# TTLclock.net
KiCad netlist of a schematic drawn in Altium Designer
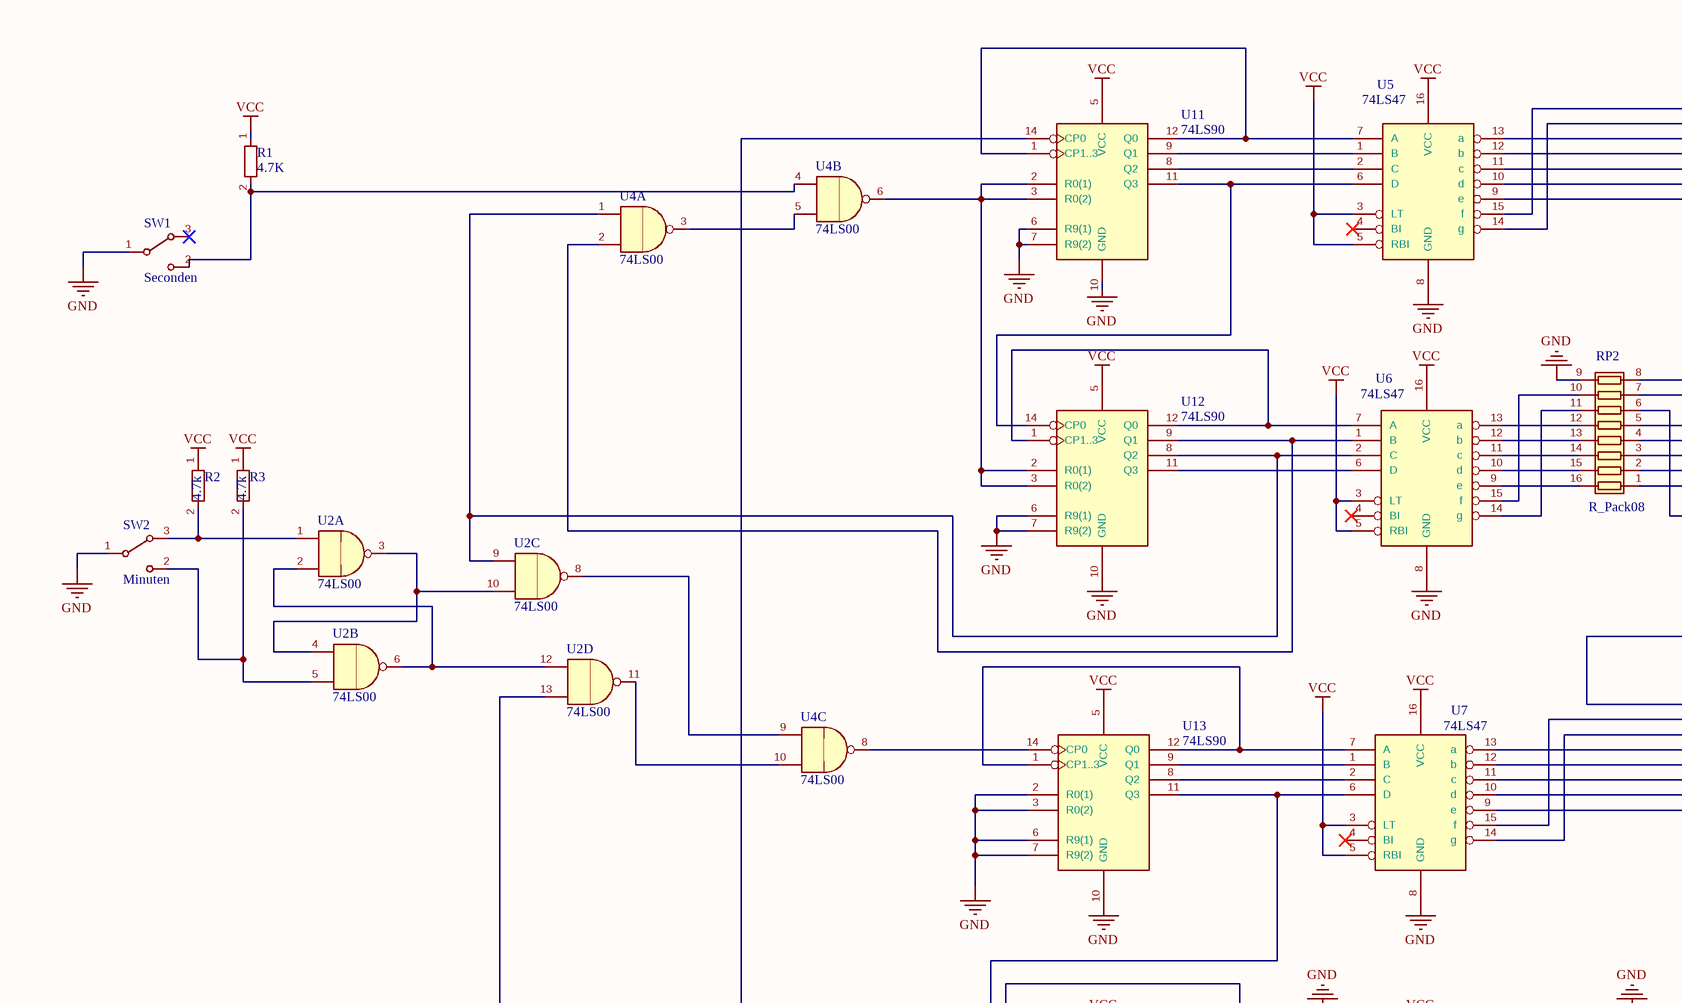
[diagram p0: TTLclock.SchDoc, top left]
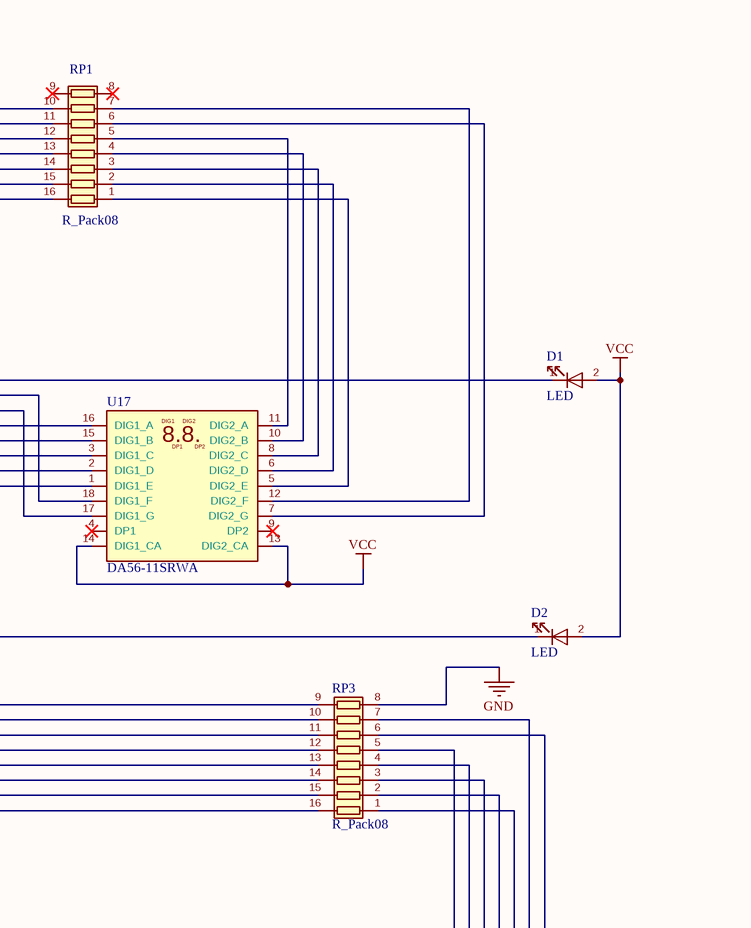
[diagram p1: TTLclock.SchDoc, top right]
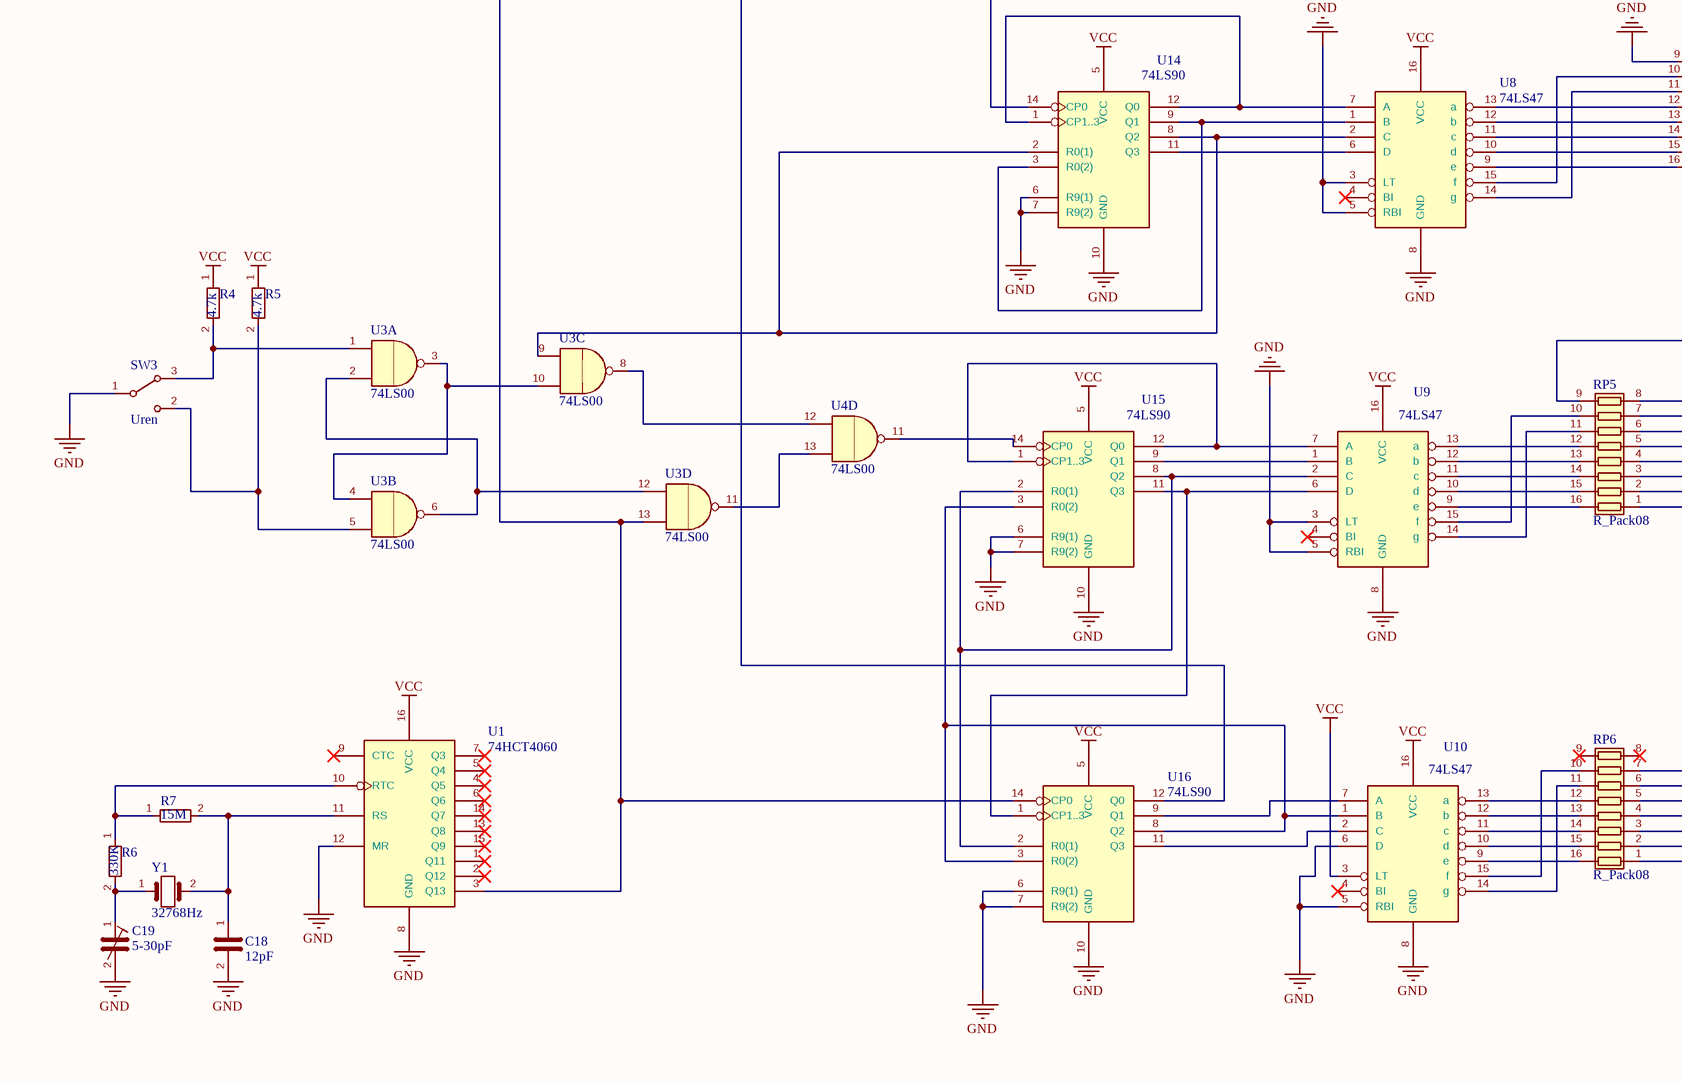
[diagram p2: TTLclock.SchDoc, bottom left]
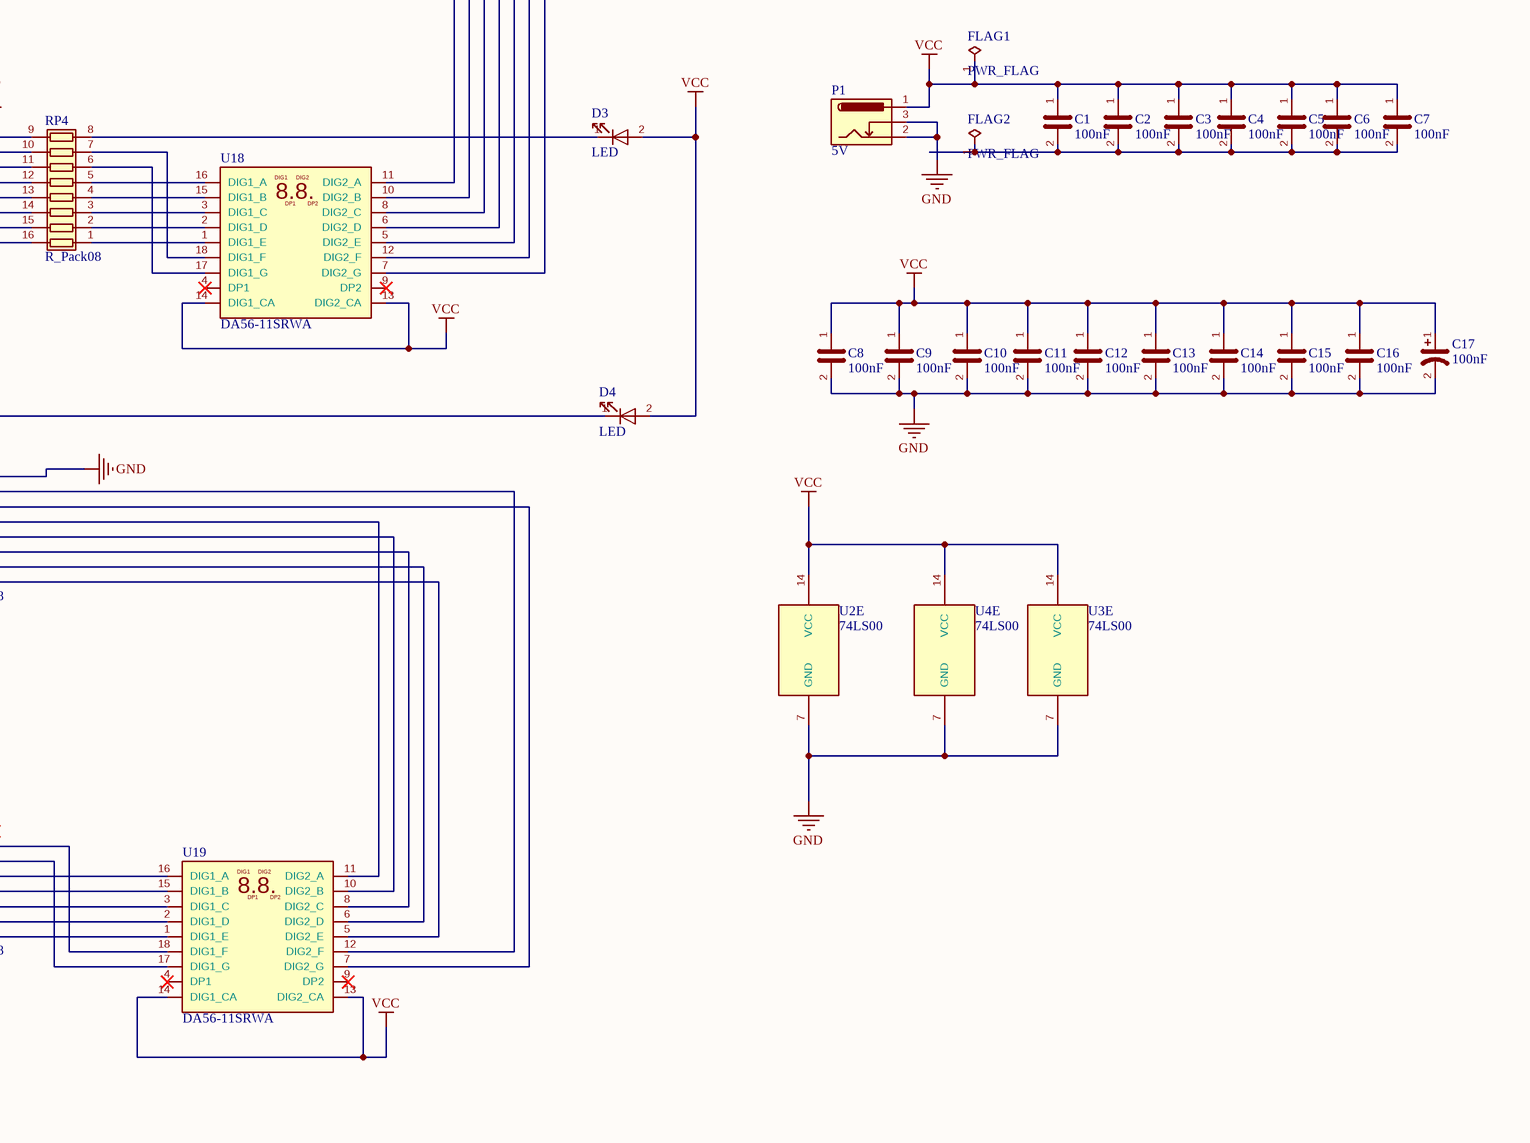
[diagram p3: TTLclock.SchDoc, bottom right]

(export (version "E")
  (design (tool "Eeschema 10.0.6"))
  (components
    (comp (ref "C1")
      (value "100nF")
      (footprint "CAPPA1420W55L380D260")
      (libsource (lib "ttl_clock") (part "C"))
    )
    (comp (ref "C2")
      (value "100nF")
      (footprint "CAPPA1420W55L380D260")
      (libsource (lib "ttl_clock") (part "C"))
    )
    (comp (ref "C3")
      (value "100nF")
      (footprint "CAPPA1420W55L380D260")
      (libsource (lib "ttl_clock") (part "C"))
    )
    (comp (ref "C4")
      (value "100nF")
      (footprint "CAPPA1420W55L380D260")
      (libsource (lib "ttl_clock") (part "C"))
    )
    (comp (ref "C5")
      (value "100nF")
      (footprint "CAPPA1420W55L380D260")
      (libsource (lib "ttl_clock") (part "C"))
    )
    (comp (ref "C6")
      (value "100nF")
      (footprint "CAPPA1420W55L380D260")
      (libsource (lib "ttl_clock") (part "C"))
    )
    (comp (ref "C7")
      (value "100nF")
      (footprint "CAPPA1420W55L380D260")
      (libsource (lib "ttl_clock") (part "C"))
    )
    (comp (ref "C8")
      (value "100nF")
      (footprint "CAPPA1420W55L380D260")
      (libsource (lib "ttl_clock") (part "C"))
    )
    (comp (ref "C9")
      (value "100nF")
      (footprint "CAPPA1420W55L380D260")
      (libsource (lib "ttl_clock") (part "C"))
    )
    (comp (ref "C10")
      (value "100nF")
      (footprint "CAPPA1420W55L380D260")
      (libsource (lib "ttl_clock") (part "C"))
    )
    (comp (ref "C11")
      (value "100nF")
      (footprint "CAPPA1420W55L380D260")
      (libsource (lib "ttl_clock") (part "C"))
    )
    (comp (ref "C12")
      (value "100nF")
      (footprint "CAPPA1420W55L380D260")
      (libsource (lib "ttl_clock") (part "C"))
    )
    (comp (ref "C13")
      (value "100nF")
      (footprint "CAPPA1420W55L380D260")
      (libsource (lib "ttl_clock") (part "C"))
    )
    (comp (ref "C14")
      (value "100nF")
      (footprint "CAPPA1420W55L380D260")
      (libsource (lib "ttl_clock") (part "C"))
    )
    (comp (ref "C15")
      (value "100nF")
      (footprint "CAPPA1420W55L380D260")
      (libsource (lib "ttl_clock") (part "C"))
    )
    (comp (ref "C16")
      (value "100nF")
      (footprint "CAPPA1420W55L380D260")
      (libsource (lib "ttl_clock") (part "C"))
    )
    (comp (ref "C17")
      (value "100nF")
      (footprint "CAPPRD250W52D630H1250")
      (libsource (lib "ttl_clock") (part "CP1"))
    )
    (comp (ref "C18") (value "12pF") (footprint "FG28") (libsource (lib "ttl_clock") (part "C")))
    (comp (ref "C19") (value "5-30pF") (footprint "JZ300") (libsource (lib "ttl_clock") (part "CTRIM")))
    (comp (ref "D1")
      (value "LED")
      (footprint "LED_SSL-LX4673GD-LA20")
      (libsource (lib "ttl_clock") (part "LED"))
    )
    (comp (ref "D2")
      (value "LED")
      (footprint "LED_SSL-LX4673GD-LA20")
      (libsource (lib "ttl_clock") (part "LED"))
    )
    (comp (ref "D3")
      (value "LED")
      (footprint "LED_SSL-LX4673GD-LA20")
      (libsource (lib "ttl_clock") (part "LED"))
    )
    (comp (ref "D4")
      (value "LED")
      (footprint "LED_SSL-LX4673GD-LA20")
      (libsource (lib "ttl_clock") (part "LED"))
    )
    (comp (ref "FLAG1") (value "PWR_FLAG") (libsource (lib "ttl_clock") (part "PWR_FLAG")))
    (comp (ref "FLAG2") (value "PWR_FLAG") (libsource (lib "ttl_clock") (part "PWR_FLAG")))
    (comp (ref "P1")
      (value "5V")
      (footprint "KLDX0202A")
      (libsource (lib "ttl_clock") (part "Barrel_Jack_Switch"))
    )
    (comp (ref "R1")
      (value "4.7K")
      (footprint "RESAD2870W80L1190D420")
      (libsource (lib "ttl_clock") (part "R"))
    )
    (comp (ref "R2")
      (value "4.7k")
      (footprint "RESAD2870W80L1190D420")
      (libsource (lib "ttl_clock") (part "R"))
    )
    (comp (ref "R3")
      (value "4.7k")
      (footprint "RESAD2870W80L1190D420")
      (libsource (lib "ttl_clock") (part "R"))
    )
    (comp (ref "R4")
      (value "4.7k")
      (footprint "RESAD2870W80L1190D420")
      (libsource (lib "ttl_clock") (part "R"))
    )
    (comp (ref "R5")
      (value "4.7k")
      (footprint "RESAD2870W80L1190D420")
      (libsource (lib "ttl_clock") (part "R"))
    )
    (comp (ref "R6")
      (value "330K")
      (footprint "RESAD2870W80L1190D420")
      (libsource (lib "ttl_clock") (part "R"))
    )
    (comp (ref "R7") (value "15M") (footprint "RESAD2870W80L1190D420") (libsource (lib "") (part "R_1")))
    (comp (ref "RP1")
      (value "R_Pack08")
      (footprint "DIP787W49P254L2197H469Q16N")
      (libsource (lib "ttl_clock") (part "R_Pack08"))
    )
    (comp (ref "RP2")
      (value "R_Pack08")
      (footprint "DIP787W49P254L2197H469Q16N")
      (libsource (lib "ttl_clock") (part "R_Pack08"))
    )
    (comp (ref "RP3")
      (value "R_Pack08")
      (footprint "DIP787W49P254L2197H469Q16N")
      (libsource (lib "ttl_clock") (part "R_Pack08"))
    )
    (comp (ref "RP4")
      (value "R_Pack08")
      (footprint "DIP787W49P254L2197H469Q16N")
      (libsource (lib "ttl_clock") (part "R_Pack08"))
    )
    (comp (ref "RP5")
      (value "R_Pack08")
      (footprint "DIP787W49P254L2197H469Q16N")
      (libsource (lib "ttl_clock") (part "R_Pack08"))
    )
    (comp (ref "RP6")
      (value "R_Pack08")
      (footprint "DIP787W49P254L2197H469Q16N")
      (libsource (lib "ttl_clock") (part "R_Pack08"))
    )
    (comp (ref "SW1")
      (value "Seconden")
      (footprint "SS0750301F040P1A")
      (libsource (lib "ttl_clock") (part "SW_SPDT_Omron"))
    )
    (comp (ref "SW2")
      (value "Minuten")
      (footprint "SS0750301F040P1A")
      (libsource (lib "ttl_clock") (part "SW_SPDT_Omron"))
    )
    (comp (ref "SW3")
      (value "Uren")
      (footprint "SS0750301F040P1A")
      (libsource (lib "ttl_clock") (part "SW_SPDT_Omron"))
    )
    (comp (ref "U1")
      (value "74HCT4060")
      (footprint "DIP794W53P254L1930H508Q16N")
      (libsource (lib "ttl_clock") (part "74HCT4060"))
    )
    (comp (ref "U2")
      (value "74LS00")
      (footprint "DIP794W53P254L1930H508Q14N")
      (libsource (lib "ttl_clock") (part "74LS00"))
    )
    (comp (ref "U3")
      (value "74LS00")
      (footprint "DIP794W53P254L1930H508Q14N")
      (libsource (lib "ttl_clock") (part "74LS00"))
    )
    (comp (ref "U4")
      (value "74LS00")
      (footprint "DIP794W53P254L1930H508Q14N")
      (libsource (lib "ttl_clock") (part "74LS00"))
    )
    (comp (ref "U5")
      (value "74LS47")
      (footprint "DIP794W53P254L1930H508Q16N")
      (libsource (lib "ttl_clock") (part "74LS47"))
    )
    (comp (ref "U6")
      (value "74LS47")
      (footprint "DIP794W53P254L1930H508Q16N")
      (libsource (lib "ttl_clock") (part "74LS47"))
    )
    (comp (ref "U7")
      (value "74LS47")
      (footprint "DIP794W53P254L1930H508Q16N")
      (libsource (lib "ttl_clock") (part "74LS47"))
    )
    (comp (ref "U8")
      (value "74LS47")
      (footprint "DIP794W53P254L1930H508Q16N")
      (libsource (lib "ttl_clock") (part "74LS47"))
    )
    (comp (ref "U9")
      (value "74LS47")
      (footprint "DIP794W53P254L1930H508Q16N")
      (libsource (lib "ttl_clock") (part "74LS47"))
    )
    (comp (ref "U10")
      (value "74LS47")
      (footprint "DIP794W53P254L1930H508Q16N")
      (libsource (lib "ttl_clock") (part "74LS47"))
    )
    (comp (ref "U11")
      (value "74LS90")
      (footprint "DIP794W53P254L1930H508Q14N")
      (libsource (lib "ttl_clock") (part "74LS90"))
    )
    (comp (ref "U12")
      (value "74LS90")
      (footprint "DIP794W53P254L1930H508Q14N")
      (libsource (lib "ttl_clock") (part "74LS90"))
    )
    (comp (ref "U13")
      (value "74LS90")
      (footprint "DIP794W53P254L1930H508Q14N")
      (libsource (lib "ttl_clock") (part "74LS90"))
    )
    (comp (ref "U14")
      (value "74LS90")
      (footprint "DIP794W53P254L1930H508Q14N")
      (libsource (lib "ttl_clock") (part "74LS90"))
    )
    (comp (ref "U15")
      (value "74LS90")
      (footprint "DIP794W53P254L1930H508Q14N")
      (libsource (lib "ttl_clock") (part "74LS90"))
    )
    (comp (ref "U16")
      (value "74LS90")
      (footprint "DIP794W53P254L1930H508Q14N")
      (libsource (lib "ttl_clock") (part "74LS90"))
    )
    (comp (ref "U17")
      (value "DA56-11SRWA")
      (footprint "DIPS1524W50P254L2500H825Q18N")
      (libsource (lib "ttl_clock") (part "DA56-11SRWA"))
    )
    (comp (ref "U18")
      (value "DA56-11SRWA")
      (footprint "DIPS1524W50P254L2500H825Q18N")
      (libsource (lib "ttl_clock") (part "DA56-11SRWA"))
    )
    (comp (ref "U19")
      (value "DA56-11SRWA")
      (footprint "DIPS1524W50P254L2500H825Q18N")
      (libsource (lib "ttl_clock") (part "DA56-11SRWA"))
    )
    (comp (ref "Y1")
      (value "32768Hz")
      (footprint "XTAL_AB26T-32.768KHZ")
      (libsource (lib "ttl_clock") (part "Crystal"))
    )
  )
  (nets
    (net (code "1") (name "GND") (class "Default")
      (node (ref "C10") (pin "2") (pinfunction "2_2") (pintype "passive"))
      (node (ref "C11") (pin "2") (pinfunction "2_2") (pintype "passive"))
      (node (ref "C12") (pin "2") (pinfunction "2_2") (pintype "passive"))
      (node (ref "C13") (pin "2") (pinfunction "2_2") (pintype "passive"))
      (node (ref "C14") (pin "2") (pinfunction "2_2") (pintype "passive"))
      (node (ref "C15") (pin "2") (pinfunction "2_2") (pintype "passive"))
      (node (ref "C16") (pin "2") (pinfunction "2_2") (pintype "passive"))
      (node (ref "C17") (pin "2") (pinfunction "2_2") (pintype "passive"))
      (node (ref "C18") (pin "2") (pinfunction "2_2") (pintype "passive"))
      (node (ref "C19") (pin "2") (pinfunction "2_2") (pintype "passive"))
      (node (ref "C8") (pin "2") (pinfunction "2_2") (pintype "passive"))
      (node (ref "C9") (pin "2") (pinfunction "2_2") (pintype "passive"))
      (node (ref "P1") (pin "2") (pinfunction "2_2") (pintype "passive"))
      (node (ref "P1") (pin "3") (pinfunction "3_3") (pintype "passive"))
      (node (ref "RP2") (pin "9") (pinfunction "R8.2_9") (pintype "passive"))
      (node (ref "RP3") (pin "8") (pinfunction "R8.1_8") (pintype "passive"))
      (node (ref "RP4") (pin "9") (pinfunction "R8.2_9") (pintype "passive"))
      (node (ref "RP5") (pin "8") (pinfunction "R8.1_8") (pintype "passive"))
      (node (ref "SW1") (pin "1") (pinfunction "B_1") (pintype "passive"))
      (node (ref "SW2") (pin "1") (pinfunction "B_1") (pintype "passive"))
      (node (ref "SW3") (pin "1") (pinfunction "B_1") (pintype "passive"))
      (node (ref "U1") (pin "12") (pinfunction "MR_12") (pintype "passive"))
      (node (ref "U1") (pin "8") (pinfunction "GND_8") (pintype "passive"))
      (node (ref "U10") (pin "5") (pinfunction "RBI_5") (pintype "passive"))
      (node (ref "U10") (pin "6") (pinfunction "D_6") (pintype "passive"))
      (node (ref "U10") (pin "8") (pinfunction "GND_8") (pintype "passive"))
      (node (ref "U11") (pin "10") (pinfunction "GND_10") (pintype "passive"))
      (node (ref "U11") (pin "6") (pinfunction "R9(1)_6") (pintype "passive"))
      (node (ref "U11") (pin "7") (pinfunction "R9(2)_7") (pintype "passive"))
      (node (ref "U12") (pin "10") (pinfunction "GND_10") (pintype "passive"))
      (node (ref "U12") (pin "6") (pinfunction "R9(1)_6") (pintype "passive"))
      (node (ref "U12") (pin "7") (pinfunction "R9(2)_7") (pintype "passive"))
      (node (ref "U13") (pin "10") (pinfunction "GND_10") (pintype "passive"))
      (node (ref "U13") (pin "2") (pinfunction "R0(1)_2") (pintype "passive"))
      (node (ref "U13") (pin "3") (pinfunction "R0(2)_3") (pintype "passive"))
      (node (ref "U13") (pin "6") (pinfunction "R9(1)_6") (pintype "passive"))
      (node (ref "U13") (pin "7") (pinfunction "R9(2)_7") (pintype "passive"))
      (node (ref "U14") (pin "10") (pinfunction "GND_10") (pintype "passive"))
      (node (ref "U14") (pin "6") (pinfunction "R9(1)_6") (pintype "passive"))
      (node (ref "U14") (pin "7") (pinfunction "R9(2)_7") (pintype "passive"))
      (node (ref "U15") (pin "10") (pinfunction "GND_10") (pintype "passive"))
      (node (ref "U15") (pin "6") (pinfunction "R9(1)_6") (pintype "passive"))
      (node (ref "U15") (pin "7") (pinfunction "R9(2)_7") (pintype "passive"))
      (node (ref "U16") (pin "10") (pinfunction "GND_10") (pintype "passive"))
      (node (ref "U16") (pin "6") (pinfunction "R9(1)_6") (pintype "passive"))
      (node (ref "U16") (pin "7") (pinfunction "R9(2)_7") (pintype "passive"))
      (node (ref "U2") (pin "7") (pinfunction "GND_7") (pintype "passive"))
      (node (ref "U3") (pin "7") (pinfunction "GND_7") (pintype "passive"))
      (node (ref "U4") (pin "7") (pinfunction "GND_7") (pintype "passive"))
      (node (ref "U5") (pin "8") (pinfunction "GND_8") (pintype "passive"))
      (node (ref "U6") (pin "8") (pinfunction "GND_8") (pintype "passive"))
      (node (ref "U7") (pin "8") (pinfunction "GND_8") (pintype "passive"))
      (node (ref "U8") (pin "3") (pinfunction "LT_3") (pintype "passive"))
      (node (ref "U8") (pin "5") (pinfunction "RBI_5") (pintype "passive"))
      (node (ref "U8") (pin "8") (pinfunction "GND_8") (pintype "passive"))
      (node (ref "U9") (pin "3") (pinfunction "LT_3") (pintype "passive"))
      (node (ref "U9") (pin "5") (pinfunction "RBI_5") (pintype "passive"))
      (node (ref "U9") (pin "8") (pinfunction "GND_8") (pintype "passive"))
    )
    (net (code "2") (name "Net-(C19-Pad1)") (class "Default")
      (node (ref "C19") (pin "1") (pinfunction "1_1") (pintype "passive"))
      (node (ref "R6") (pin "2") (pinfunction "2_2") (pintype "passive"))
      (node (ref "Y1") (pin "1") (pinfunction "1_1") (pintype "passive"))
    )
    (net (code "3") (name "Net-(D1-K)") (class "Default")
      (node (ref "D1") (pin "1") (pinfunction "K_1") (pintype "passive"))
      (node (ref "RP2") (pin "8") (pinfunction "R8.1_8") (pintype "passive"))
    )
    (net (code "4") (name "Net-(D2-K)") (class "Default")
      (node (ref "D2") (pin "1") (pinfunction "K_1") (pintype "passive"))
      (node (ref "RP3") (pin "9") (pinfunction "R8.2_9") (pintype "passive"))
    )
    (net (code "5") (name "Net-(D3-K)") (class "Default")
      (node (ref "D3") (pin "1") (pinfunction "K_1") (pintype "passive"))
      (node (ref "RP4") (pin "8") (pinfunction "R8.1_8") (pintype "passive"))
    )
    (net (code "6") (name "Net-(D4-K)") (class "Default")
      (node (ref "D4") (pin "1") (pinfunction "K_1") (pintype "passive"))
      (node (ref "RP5") (pin "9") (pinfunction "R8.2_9") (pintype "passive"))
    )
    (net (code "7") (name "Net-(FLAG2-pwr)") (class "Default")
      (node (ref "C1") (pin "2") (pinfunction "2_2") (pintype "passive"))
      (node (ref "C2") (pin "2") (pinfunction "2_2") (pintype "passive"))
      (node (ref "C3") (pin "2") (pinfunction "2_2") (pintype "passive"))
      (node (ref "C4") (pin "2") (pinfunction "2_2") (pintype "passive"))
      (node (ref "C5") (pin "2") (pinfunction "2_2") (pintype "passive"))
      (node (ref "C6") (pin "2") (pinfunction "2_2") (pintype "passive"))
      (node (ref "C7") (pin "2") (pinfunction "2_2") (pintype "passive"))
      (node (ref "FLAG2") (pin "1") (pinfunction "pwr_1") (pintype "passive"))
    )
    (net (code "8") (name "Net-(RP1-R1.1)") (class "Default")
      (node (ref "RP1") (pin "1") (pinfunction "R1.1_1") (pintype "passive"))
      (node (ref "U17") (pin "5") (pinfunction "DIG2_E_5") (pintype "passive"))
    )
    (net (code "9") (name "Net-(RP1-R1.2)") (class "Default")
      (node (ref "RP1") (pin "16") (pinfunction "R1.2_16") (pintype "passive"))
      (node (ref "U5") (pin "9") (pinfunction "e_9") (pintype "passive"))
    )
    (net (code "10") (name "Net-(RP1-R2.1)") (class "Default")
      (node (ref "RP1") (pin "2") (pinfunction "R2.1_2") (pintype "passive"))
      (node (ref "U17") (pin "6") (pinfunction "DIG2_D_6") (pintype "passive"))
    )
    (net (code "11") (name "Net-(RP1-R2.2)") (class "Default")
      (node (ref "RP1") (pin "15") (pinfunction "R2.2_15") (pintype "passive"))
      (node (ref "U5") (pin "10") (pinfunction "d_10") (pintype "passive"))
    )
    (net (code "12") (name "Net-(RP1-R3.1)") (class "Default")
      (node (ref "RP1") (pin "3") (pinfunction "R3.1_3") (pintype "passive"))
      (node (ref "U17") (pin "8") (pinfunction "DIG2_C_8") (pintype "passive"))
    )
    (net (code "13") (name "Net-(RP1-R3.2)") (class "Default")
      (node (ref "RP1") (pin "14") (pinfunction "R3.2_14") (pintype "passive"))
      (node (ref "U5") (pin "11") (pinfunction "c_11") (pintype "passive"))
    )
    (net (code "14") (name "Net-(RP1-R4.1)") (class "Default")
      (node (ref "RP1") (pin "4") (pinfunction "R4.1_4") (pintype "passive"))
      (node (ref "U17") (pin "10") (pinfunction "DIG2_B_10") (pintype "passive"))
    )
    (net (code "15") (name "Net-(RP1-R4.2)") (class "Default")
      (node (ref "RP1") (pin "13") (pinfunction "R4.2_13") (pintype "passive"))
      (node (ref "U5") (pin "12") (pinfunction "b_12") (pintype "passive"))
    )
    (net (code "16") (name "Net-(RP1-R5.1)") (class "Default")
      (node (ref "RP1") (pin "5") (pinfunction "R5.1_5") (pintype "passive"))
      (node (ref "U17") (pin "11") (pinfunction "DIG2_A_11") (pintype "passive"))
    )
    (net (code "17") (name "Net-(RP1-R5.2)") (class "Default")
      (node (ref "RP1") (pin "12") (pinfunction "R5.2_12") (pintype "passive"))
      (node (ref "U5") (pin "13") (pinfunction "a_13") (pintype "passive"))
    )
    (net (code "18") (name "Net-(RP1-R6.1)") (class "Default")
      (node (ref "RP1") (pin "6") (pinfunction "R6.1_6") (pintype "passive"))
      (node (ref "U17") (pin "7") (pinfunction "DIG2_G_7") (pintype "passive"))
    )
    (net (code "19") (name "Net-(RP1-R6.2)") (class "Default")
      (node (ref "RP1") (pin "11") (pinfunction "R6.2_11") (pintype "passive"))
      (node (ref "U5") (pin "14") (pinfunction "g_14") (pintype "passive"))
    )
    (net (code "20") (name "Net-(RP1-R7.1)") (class "Default")
      (node (ref "RP1") (pin "7") (pinfunction "R7.1_7") (pintype "passive"))
      (node (ref "U17") (pin "12") (pinfunction "DIG2_F_12") (pintype "passive"))
    )
    (net (code "21") (name "Net-(RP1-R7.2)") (class "Default")
      (node (ref "RP1") (pin "10") (pinfunction "R7.2_10") (pintype "passive"))
      (node (ref "U5") (pin "15") (pinfunction "f_15") (pintype "passive"))
    )
    (net (code "22") (name "Net-(RP2-R1.1)") (class "Default")
      (node (ref "RP2") (pin "1") (pinfunction "R1.1_1") (pintype "passive"))
      (node (ref "U17") (pin "1") (pinfunction "DIG1_E_1") (pintype "passive"))
    )
    (net (code "23") (name "Net-(RP2-R1.2)") (class "Default")
      (node (ref "RP2") (pin "16") (pinfunction "R1.2_16") (pintype "passive"))
      (node (ref "U6") (pin "9") (pinfunction "e_9") (pintype "passive"))
    )
    (net (code "24") (name "Net-(RP2-R2.1)") (class "Default")
      (node (ref "RP2") (pin "2") (pinfunction "R2.1_2") (pintype "passive"))
      (node (ref "U17") (pin "2") (pinfunction "DIG1_D_2") (pintype "passive"))
    )
    (net (code "25") (name "Net-(RP2-R2.2)") (class "Default")
      (node (ref "RP2") (pin "15") (pinfunction "R2.2_15") (pintype "passive"))
      (node (ref "U6") (pin "10") (pinfunction "d_10") (pintype "passive"))
    )
    (net (code "26") (name "Net-(RP2-R3.1)") (class "Default")
      (node (ref "RP2") (pin "3") (pinfunction "R3.1_3") (pintype "passive"))
      (node (ref "U17") (pin "3") (pinfunction "DIG1_C_3") (pintype "passive"))
    )
    (net (code "27") (name "Net-(RP2-R3.2)") (class "Default")
      (node (ref "RP2") (pin "14") (pinfunction "R3.2_14") (pintype "passive"))
      (node (ref "U6") (pin "11") (pinfunction "c_11") (pintype "passive"))
    )
    (net (code "28") (name "Net-(RP2-R4.1)") (class "Default")
      (node (ref "RP2") (pin "4") (pinfunction "R4.1_4") (pintype "passive"))
      (node (ref "U17") (pin "15") (pinfunction "DIG1_B_15") (pintype "passive"))
    )
    (net (code "29") (name "Net-(RP2-R4.2)") (class "Default")
      (node (ref "RP2") (pin "13") (pinfunction "R4.2_13") (pintype "passive"))
      (node (ref "U6") (pin "12") (pinfunction "b_12") (pintype "passive"))
    )
    (net (code "30") (name "Net-(RP2-R5.1)") (class "Default")
      (node (ref "RP2") (pin "5") (pinfunction "R5.1_5") (pintype "passive"))
      (node (ref "U17") (pin "16") (pinfunction "DIG1_A_16") (pintype "passive"))
    )
    (net (code "31") (name "Net-(RP2-R5.2)") (class "Default")
      (node (ref "RP2") (pin "12") (pinfunction "R5.2_12") (pintype "passive"))
      (node (ref "U6") (pin "13") (pinfunction "a_13") (pintype "passive"))
    )
    (net (code "32") (name "Net-(RP2-R6.1)") (class "Default")
      (node (ref "RP2") (pin "6") (pinfunction "R6.1_6") (pintype "passive"))
      (node (ref "U17") (pin "17") (pinfunction "DIG1_G_17") (pintype "passive"))
    )
    (net (code "33") (name "Net-(RP2-R6.2)") (class "Default")
      (node (ref "RP2") (pin "11") (pinfunction "R6.2_11") (pintype "passive"))
      (node (ref "U6") (pin "14") (pinfunction "g_14") (pintype "passive"))
    )
    (net (code "34") (name "Net-(RP2-R7.1)") (class "Default")
      (node (ref "RP2") (pin "7") (pinfunction "R7.1_7") (pintype "passive"))
      (node (ref "U17") (pin "18") (pinfunction "DIG1_F_18") (pintype "passive"))
    )
    (net (code "35") (name "Net-(RP2-R7.2)") (class "Default")
      (node (ref "RP2") (pin "10") (pinfunction "R7.2_10") (pintype "passive"))
      (node (ref "U6") (pin "15") (pinfunction "f_15") (pintype "passive"))
    )
    (net (code "36") (name "Net-(RP3-R1.1)") (class "Default")
      (node (ref "RP3") (pin "1") (pinfunction "R1.1_1") (pintype "passive"))
      (node (ref "U18") (pin "5") (pinfunction "DIG2_E_5") (pintype "passive"))
    )
    (net (code "37") (name "Net-(RP3-R1.2)") (class "Default")
      (node (ref "RP3") (pin "16") (pinfunction "R1.2_16") (pintype "passive"))
      (node (ref "U7") (pin "9") (pinfunction "e_9") (pintype "passive"))
    )
    (net (code "38") (name "Net-(RP3-R2.1)") (class "Default")
      (node (ref "RP3") (pin "2") (pinfunction "R2.1_2") (pintype "passive"))
      (node (ref "U18") (pin "6") (pinfunction "DIG2_D_6") (pintype "passive"))
    )
    (net (code "39") (name "Net-(RP3-R2.2)") (class "Default")
      (node (ref "RP3") (pin "15") (pinfunction "R2.2_15") (pintype "passive"))
      (node (ref "U7") (pin "10") (pinfunction "d_10") (pintype "passive"))
    )
    (net (code "40") (name "Net-(RP3-R3.1)") (class "Default")
      (node (ref "RP3") (pin "3") (pinfunction "R3.1_3") (pintype "passive"))
      (node (ref "U18") (pin "8") (pinfunction "DIG2_C_8") (pintype "passive"))
    )
    (net (code "41") (name "Net-(RP3-R3.2)") (class "Default")
      (node (ref "RP3") (pin "14") (pinfunction "R3.2_14") (pintype "passive"))
      (node (ref "U7") (pin "11") (pinfunction "c_11") (pintype "passive"))
    )
    (net (code "42") (name "Net-(RP3-R4.1)") (class "Default")
      (node (ref "RP3") (pin "4") (pinfunction "R4.1_4") (pintype "passive"))
      (node (ref "U18") (pin "10") (pinfunction "DIG2_B_10") (pintype "passive"))
    )
    (net (code "43") (name "Net-(RP3-R4.2)") (class "Default")
      (node (ref "RP3") (pin "13") (pinfunction "R4.2_13") (pintype "passive"))
      (node (ref "U7") (pin "12") (pinfunction "b_12") (pintype "passive"))
    )
    (net (code "44") (name "Net-(RP3-R5.1)") (class "Default")
      (node (ref "RP3") (pin "5") (pinfunction "R5.1_5") (pintype "passive"))
      (node (ref "U18") (pin "11") (pinfunction "DIG2_A_11") (pintype "passive"))
    )
    (net (code "45") (name "Net-(RP3-R5.2)") (class "Default")
      (node (ref "RP3") (pin "12") (pinfunction "R5.2_12") (pintype "passive"))
      (node (ref "U7") (pin "13") (pinfunction "a_13") (pintype "passive"))
    )
    (net (code "46") (name "Net-(RP3-R6.1)") (class "Default")
      (node (ref "RP3") (pin "6") (pinfunction "R6.1_6") (pintype "passive"))
      (node (ref "U18") (pin "7") (pinfunction "DIG2_G_7") (pintype "passive"))
    )
    (net (code "47") (name "Net-(RP3-R6.2)") (class "Default")
      (node (ref "RP3") (pin "11") (pinfunction "R6.2_11") (pintype "passive"))
      (node (ref "U7") (pin "14") (pinfunction "g_14") (pintype "passive"))
    )
    (net (code "48") (name "Net-(RP3-R7.1)") (class "Default")
      (node (ref "RP3") (pin "7") (pinfunction "R7.1_7") (pintype "passive"))
      (node (ref "U18") (pin "12") (pinfunction "DIG2_F_12") (pintype "passive"))
    )
    (net (code "49") (name "Net-(RP3-R7.2)") (class "Default")
      (node (ref "RP3") (pin "10") (pinfunction "R7.2_10") (pintype "passive"))
      (node (ref "U7") (pin "15") (pinfunction "f_15") (pintype "passive"))
    )
    (net (code "50") (name "Net-(RP4-R1.1)") (class "Default")
      (node (ref "RP4") (pin "1") (pinfunction "R1.1_1") (pintype "passive"))
      (node (ref "U18") (pin "1") (pinfunction "DIG1_E_1") (pintype "passive"))
    )
    (net (code "51") (name "Net-(RP4-R1.2)") (class "Default")
      (node (ref "RP4") (pin "16") (pinfunction "R1.2_16") (pintype "passive"))
      (node (ref "U8") (pin "9") (pinfunction "e_9") (pintype "passive"))
    )
    (net (code "52") (name "Net-(RP4-R2.1)") (class "Default")
      (node (ref "RP4") (pin "2") (pinfunction "R2.1_2") (pintype "passive"))
      (node (ref "U18") (pin "2") (pinfunction "DIG1_D_2") (pintype "passive"))
    )
    (net (code "53") (name "Net-(RP4-R2.2)") (class "Default")
      (node (ref "RP4") (pin "15") (pinfunction "R2.2_15") (pintype "passive"))
      (node (ref "U8") (pin "10") (pinfunction "d_10") (pintype "passive"))
    )
    (net (code "54") (name "Net-(RP4-R3.1)") (class "Default")
      (node (ref "RP4") (pin "3") (pinfunction "R3.1_3") (pintype "passive"))
      (node (ref "U18") (pin "3") (pinfunction "DIG1_C_3") (pintype "passive"))
    )
    (net (code "55") (name "Net-(RP4-R3.2)") (class "Default")
      (node (ref "RP4") (pin "14") (pinfunction "R3.2_14") (pintype "passive"))
      (node (ref "U8") (pin "11") (pinfunction "c_11") (pintype "passive"))
    )
    (net (code "56") (name "Net-(RP4-R4.1)") (class "Default")
      (node (ref "RP4") (pin "4") (pinfunction "R4.1_4") (pintype "passive"))
      (node (ref "U18") (pin "15") (pinfunction "DIG1_B_15") (pintype "passive"))
    )
    (net (code "57") (name "Net-(RP4-R4.2)") (class "Default")
      (node (ref "RP4") (pin "13") (pinfunction "R4.2_13") (pintype "passive"))
      (node (ref "U8") (pin "12") (pinfunction "b_12") (pintype "passive"))
    )
    (net (code "58") (name "Net-(RP4-R5.1)") (class "Default")
      (node (ref "RP4") (pin "5") (pinfunction "R5.1_5") (pintype "passive"))
      (node (ref "U18") (pin "16") (pinfunction "DIG1_A_16") (pintype "passive"))
    )
    (net (code "59") (name "Net-(RP4-R5.2)") (class "Default")
      (node (ref "RP4") (pin "12") (pinfunction "R5.2_12") (pintype "passive"))
      (node (ref "U8") (pin "13") (pinfunction "a_13") (pintype "passive"))
    )
    (net (code "60") (name "Net-(RP4-R6.1)") (class "Default")
      (node (ref "RP4") (pin "6") (pinfunction "R6.1_6") (pintype "passive"))
      (node (ref "U18") (pin "17") (pinfunction "DIG1_G_17") (pintype "passive"))
    )
    (net (code "61") (name "Net-(RP4-R6.2)") (class "Default")
      (node (ref "RP4") (pin "11") (pinfunction "R6.2_11") (pintype "passive"))
      (node (ref "U8") (pin "14") (pinfunction "g_14") (pintype "passive"))
    )
    (net (code "62") (name "Net-(RP4-R7.1)") (class "Default")
      (node (ref "RP4") (pin "7") (pinfunction "R7.1_7") (pintype "passive"))
      (node (ref "U18") (pin "18") (pinfunction "DIG1_F_18") (pintype "passive"))
    )
    (net (code "63") (name "Net-(RP4-R7.2)") (class "Default")
      (node (ref "RP4") (pin "10") (pinfunction "R7.2_10") (pintype "passive"))
      (node (ref "U8") (pin "15") (pinfunction "f_15") (pintype "passive"))
    )
    (net (code "64") (name "Net-(RP5-R1.1)") (class "Default")
      (node (ref "RP5") (pin "1") (pinfunction "R1.1_1") (pintype "passive"))
      (node (ref "U19") (pin "5") (pinfunction "DIG2_E_5") (pintype "passive"))
    )
    (net (code "65") (name "Net-(RP5-R1.2)") (class "Default")
      (node (ref "RP5") (pin "16") (pinfunction "R1.2_16") (pintype "passive"))
      (node (ref "U9") (pin "9") (pinfunction "e_9") (pintype "passive"))
    )
    (net (code "66") (name "Net-(RP5-R2.1)") (class "Default")
      (node (ref "RP5") (pin "2") (pinfunction "R2.1_2") (pintype "passive"))
      (node (ref "U19") (pin "6") (pinfunction "DIG2_D_6") (pintype "passive"))
    )
    (net (code "67") (name "Net-(RP5-R2.2)") (class "Default")
      (node (ref "RP5") (pin "15") (pinfunction "R2.2_15") (pintype "passive"))
      (node (ref "U9") (pin "10") (pinfunction "d_10") (pintype "passive"))
    )
    (net (code "68") (name "Net-(RP5-R3.1)") (class "Default")
      (node (ref "RP5") (pin "3") (pinfunction "R3.1_3") (pintype "passive"))
      (node (ref "U19") (pin "8") (pinfunction "DIG2_C_8") (pintype "passive"))
    )
    (net (code "69") (name "Net-(RP5-R3.2)") (class "Default")
      (node (ref "RP5") (pin "14") (pinfunction "R3.2_14") (pintype "passive"))
      (node (ref "U9") (pin "11") (pinfunction "c_11") (pintype "passive"))
    )
    (net (code "70") (name "Net-(RP5-R4.1)") (class "Default")
      (node (ref "RP5") (pin "4") (pinfunction "R4.1_4") (pintype "passive"))
      (node (ref "U19") (pin "10") (pinfunction "DIG2_B_10") (pintype "passive"))
    )
    (net (code "71") (name "Net-(RP5-R4.2)") (class "Default")
      (node (ref "RP5") (pin "13") (pinfunction "R4.2_13") (pintype "passive"))
      (node (ref "U9") (pin "12") (pinfunction "b_12") (pintype "passive"))
    )
    (net (code "72") (name "Net-(RP5-R5.1)") (class "Default")
      (node (ref "RP5") (pin "5") (pinfunction "R5.1_5") (pintype "passive"))
      (node (ref "U19") (pin "11") (pinfunction "DIG2_A_11") (pintype "passive"))
    )
    (net (code "73") (name "Net-(RP5-R5.2)") (class "Default")
      (node (ref "RP5") (pin "12") (pinfunction "R5.2_12") (pintype "passive"))
      (node (ref "U9") (pin "13") (pinfunction "a_13") (pintype "passive"))
    )
    (net (code "74") (name "Net-(RP5-R6.1)") (class "Default")
      (node (ref "RP5") (pin "6") (pinfunction "R6.1_6") (pintype "passive"))
      (node (ref "U19") (pin "7") (pinfunction "DIG2_G_7") (pintype "passive"))
    )
    (net (code "75") (name "Net-(RP5-R6.2)") (class "Default")
      (node (ref "RP5") (pin "11") (pinfunction "R6.2_11") (pintype "passive"))
      (node (ref "U9") (pin "14") (pinfunction "g_14") (pintype "passive"))
    )
    (net (code "76") (name "Net-(RP5-R7.1)") (class "Default")
      (node (ref "RP5") (pin "7") (pinfunction "R7.1_7") (pintype "passive"))
      (node (ref "U19") (pin "12") (pinfunction "DIG2_F_12") (pintype "passive"))
    )
    (net (code "77") (name "Net-(RP5-R7.2)") (class "Default")
      (node (ref "RP5") (pin "10") (pinfunction "R7.2_10") (pintype "passive"))
      (node (ref "U9") (pin "15") (pinfunction "f_15") (pintype "passive"))
    )
    (net (code "78") (name "Net-(RP6-R1.1)") (class "Default")
      (node (ref "RP6") (pin "1") (pinfunction "R1.1_1") (pintype "passive"))
      (node (ref "U19") (pin "1") (pinfunction "DIG1_E_1") (pintype "passive"))
    )
    (net (code "79") (name "Net-(RP6-R1.2)") (class "Default")
      (node (ref "RP6") (pin "16") (pinfunction "R1.2_16") (pintype "passive"))
      (node (ref "U10") (pin "9") (pinfunction "e_9") (pintype "passive"))
    )
    (net (code "80") (name "Net-(RP6-R2.1)") (class "Default")
      (node (ref "RP6") (pin "2") (pinfunction "R2.1_2") (pintype "passive"))
      (node (ref "U19") (pin "2") (pinfunction "DIG1_D_2") (pintype "passive"))
    )
    (net (code "81") (name "Net-(RP6-R2.2)") (class "Default")
      (node (ref "RP6") (pin "15") (pinfunction "R2.2_15") (pintype "passive"))
      (node (ref "U10") (pin "10") (pinfunction "d_10") (pintype "passive"))
    )
    (net (code "82") (name "Net-(RP6-R3.1)") (class "Default")
      (node (ref "RP6") (pin "3") (pinfunction "R3.1_3") (pintype "passive"))
      (node (ref "U19") (pin "3") (pinfunction "DIG1_C_3") (pintype "passive"))
    )
    (net (code "83") (name "Net-(RP6-R3.2)") (class "Default")
      (node (ref "RP6") (pin "14") (pinfunction "R3.2_14") (pintype "passive"))
      (node (ref "U10") (pin "11") (pinfunction "c_11") (pintype "passive"))
    )
    (net (code "84") (name "Net-(RP6-R4.1)") (class "Default")
      (node (ref "RP6") (pin "4") (pinfunction "R4.1_4") (pintype "passive"))
      (node (ref "U19") (pin "15") (pinfunction "DIG1_B_15") (pintype "passive"))
    )
    (net (code "85") (name "Net-(RP6-R4.2)") (class "Default")
      (node (ref "RP6") (pin "13") (pinfunction "R4.2_13") (pintype "passive"))
      (node (ref "U10") (pin "12") (pinfunction "b_12") (pintype "passive"))
    )
    (net (code "86") (name "Net-(RP6-R5.1)") (class "Default")
      (node (ref "RP6") (pin "5") (pinfunction "R5.1_5") (pintype "passive"))
      (node (ref "U19") (pin "16") (pinfunction "DIG1_A_16") (pintype "passive"))
    )
    (net (code "87") (name "Net-(RP6-R5.2)") (class "Default")
      (node (ref "RP6") (pin "12") (pinfunction "R5.2_12") (pintype "passive"))
      (node (ref "U10") (pin "13") (pinfunction "a_13") (pintype "passive"))
    )
    (net (code "88") (name "Net-(RP6-R6.1)") (class "Default")
      (node (ref "RP6") (pin "6") (pinfunction "R6.1_6") (pintype "passive"))
      (node (ref "U19") (pin "17") (pinfunction "DIG1_G_17") (pintype "passive"))
    )
    (net (code "89") (name "Net-(RP6-R6.2)") (class "Default")
      (node (ref "RP6") (pin "11") (pinfunction "R6.2_11") (pintype "passive"))
      (node (ref "U10") (pin "14") (pinfunction "g_14") (pintype "passive"))
    )
    (net (code "90") (name "Net-(RP6-R7.1)") (class "Default")
      (node (ref "RP6") (pin "7") (pinfunction "R7.1_7") (pintype "passive"))
      (node (ref "U19") (pin "18") (pinfunction "DIG1_F_18") (pintype "passive"))
    )
    (net (code "91") (name "Net-(RP6-R7.2)") (class "Default")
      (node (ref "RP6") (pin "10") (pinfunction "R7.2_10") (pintype "passive"))
      (node (ref "U10") (pin "15") (pinfunction "f_15") (pintype "passive"))
    )
    (net (code "92") (name "Net-(SW1-C)") (class "Default")
      (node (ref "R1") (pin "2") (pinfunction "2_2") (pintype "passive"))
      (node (ref "SW1") (pin "2") (pinfunction "C_2") (pintype "passive"))
      (node (ref "U4") (pin "4") (pinfunction "4_4") (pintype "passive"))
    )
    (net (code "93") (name "Net-(SW2-A)") (class "Default")
      (node (ref "R2") (pin "2") (pinfunction "2_2") (pintype "passive"))
      (node (ref "SW2") (pin "3") (pinfunction "A_3") (pintype "passive"))
      (node (ref "U2") (pin "1") (pinfunction "1_1") (pintype "passive"))
    )
    (net (code "94") (name "Net-(SW2-C)") (class "Default")
      (node (ref "R3") (pin "2") (pinfunction "2_2") (pintype "passive"))
      (node (ref "SW2") (pin "2") (pinfunction "C_2") (pintype "passive"))
      (node (ref "U2") (pin "5") (pinfunction "5_5") (pintype "passive"))
    )
    (net (code "95") (name "Net-(SW3-A)") (class "Default")
      (node (ref "R4") (pin "2") (pinfunction "2_2") (pintype "passive"))
      (node (ref "SW3") (pin "3") (pinfunction "A_3") (pintype "passive"))
      (node (ref "U3") (pin "1") (pinfunction "1_1") (pintype "passive"))
    )
    (net (code "96") (name "Net-(SW3-C)") (class "Default")
      (node (ref "R5") (pin "2") (pinfunction "2_2") (pintype "passive"))
      (node (ref "SW3") (pin "2") (pinfunction "C_2") (pintype "passive"))
      (node (ref "U3") (pin "5") (pinfunction "5_5") (pintype "passive"))
    )
    (net (code "97") (name "Net-(U1-Q13)") (class "Default")
      (node (ref "U1") (pin "3") (pinfunction "Q13_3") (pintype "passive"))
      (node (ref "U16") (pin "14") (pinfunction "CP0_14") (pintype "passive"))
      (node (ref "U2") (pin "13") (pinfunction "13_13") (pintype "passive"))
      (node (ref "U3") (pin "13") (pinfunction "13_13") (pintype "passive"))
    )
    (net (code "98") (name "Net-(U1-RS)") (class "Default")
      (node (ref "C18") (pin "1") (pinfunction "1_1") (pintype "passive"))
      (node (ref "R7") (pin "2") (pinfunction "2_2") (pintype "passive"))
      (node (ref "U1") (pin "11") (pinfunction "RS_11") (pintype "passive"))
      (node (ref "Y1") (pin "2") (pinfunction "2_2") (pintype "passive"))
    )
    (net (code "99") (name "Net-(U1-RTC)") (class "Default")
      (node (ref "R6") (pin "1") (pinfunction "1_1") (pintype "passive"))
      (node (ref "R7") (pin "1") (pinfunction "1_1") (pintype "passive"))
      (node (ref "U1") (pin "10") (pinfunction "RTC_10") (pintype "passive"))
    )
    (net (code "100") (name "Net-(U2-Pad8)") (class "Default")
      (node (ref "U2") (pin "8") (pinfunction "8_8") (pintype "passive"))
      (node (ref "U4") (pin "9") (pinfunction "9_9") (pintype "passive"))
    )
    (net (code "101") (name "Net-(U2-Pad10)") (class "Default")
      (node (ref "U2") (pin "10") (pinfunction "10_10") (pintype "passive"))
      (node (ref "U2") (pin "3") (pinfunction "3_3") (pintype "passive"))
      (node (ref "U2") (pin "4") (pinfunction "4_4") (pintype "passive"))
    )
    (net (code "102") (name "Net-(U2-Pad11)") (class "Default")
      (node (ref "U2") (pin "11") (pinfunction "11_11") (pintype "passive"))
      (node (ref "U4") (pin "10") (pinfunction "10_10") (pintype "passive"))
    )
    (net (code "103") (name "Net-(U2-Pad12)") (class "Default")
      (node (ref "U2") (pin "12") (pinfunction "12_12") (pintype "passive"))
      (node (ref "U2") (pin "2") (pinfunction "2_2") (pintype "passive"))
      (node (ref "U2") (pin "6") (pinfunction "6_6") (pintype "passive"))
    )
    (net (code "104") (name "Net-(U3-Pad8)") (class "Default")
      (node (ref "U3") (pin "8") (pinfunction "8_8") (pintype "passive"))
      (node (ref "U4") (pin "12") (pinfunction "12_12") (pintype "passive"))
    )
    (net (code "105") (name "Net-(U3-Pad10)") (class "Default")
      (node (ref "U3") (pin "10") (pinfunction "10_10") (pintype "passive"))
      (node (ref "U3") (pin "3") (pinfunction "3_3") (pintype "passive"))
      (node (ref "U3") (pin "4") (pinfunction "4_4") (pintype "passive"))
    )
    (net (code "106") (name "Net-(U3-Pad11)") (class "Default")
      (node (ref "U3") (pin "11") (pinfunction "11_11") (pintype "passive"))
      (node (ref "U4") (pin "13") (pinfunction "13_13") (pintype "passive"))
    )
    (net (code "107") (name "Net-(U3-Pad12)") (class "Default")
      (node (ref "U3") (pin "12") (pinfunction "12_12") (pintype "passive"))
      (node (ref "U3") (pin "2") (pinfunction "2_2") (pintype "passive"))
      (node (ref "U3") (pin "6") (pinfunction "6_6") (pintype "passive"))
    )
    (net (code "108") (name "Net-(U4-Pad3)") (class "Default")
      (node (ref "U4") (pin "3") (pinfunction "3_3") (pintype "passive"))
      (node (ref "U4") (pin "5") (pinfunction "5_5") (pintype "passive"))
    )
    (net (code "109") (name "Net-(U10-A)") (class "Default")
      (node (ref "U10") (pin "7") (pinfunction "A_7") (pintype "passive"))
      (node (ref "U16") (pin "9") (pinfunction "Q1_9") (pintype "passive"))
    )
    (net (code "110") (name "Net-(U10-B)") (class "Default")
      (node (ref "U10") (pin "1") (pinfunction "B_1") (pintype "passive"))
      (node (ref "U15") (pin "3") (pinfunction "R0(2)_3") (pintype "passive"))
      (node (ref "U16") (pin "3") (pinfunction "R0(2)_3") (pintype "passive"))
      (node (ref "U16") (pin "8") (pinfunction "Q2_8") (pintype "passive"))
    )
    (net (code "111") (name "Net-(U10-C)") (class "Default")
      (node (ref "U10") (pin "2") (pinfunction "C_2") (pintype "passive"))
      (node (ref "U16") (pin "11") (pinfunction "Q3_11") (pintype "passive"))
    )
    (net (code "112") (name "Net-(U11-CP0)") (class "Default")
      (node (ref "U11") (pin "14") (pinfunction "CP0_14") (pintype "passive"))
      (node (ref "U16") (pin "12") (pinfunction "Q0_12") (pintype "passive"))
    )
    (net (code "113") (name "Net-(U11-CP1..3)") (class "Default")
      (node (ref "U11") (pin "1") (pinfunction "CP1..3_1") (pintype "passive"))
      (node (ref "U11") (pin "12") (pinfunction "Q0_12") (pintype "passive"))
      (node (ref "U5") (pin "7") (pinfunction "A_7") (pintype "passive"))
    )
    (net (code "114") (name "Net-(U11-Q1)") (class "Default")
      (node (ref "U11") (pin "9") (pinfunction "Q1_9") (pintype "passive"))
      (node (ref "U5") (pin "1") (pinfunction "B_1") (pintype "passive"))
    )
    (net (code "115") (name "Net-(U11-Q2)") (class "Default")
      (node (ref "U11") (pin "8") (pinfunction "Q2_8") (pintype "passive"))
      (node (ref "U5") (pin "2") (pinfunction "C_2") (pintype "passive"))
    )
    (net (code "116") (name "Net-(U11-Q3)") (class "Default")
      (node (ref "U11") (pin "11") (pinfunction "Q3_11") (pintype "passive"))
      (node (ref "U12") (pin "14") (pinfunction "CP0_14") (pintype "passive"))
      (node (ref "U5") (pin "6") (pinfunction "D_6") (pintype "passive"))
    )
    (net (code "117") (name "Net-(U11-R0(1))") (class "Default")
      (node (ref "U11") (pin "2") (pinfunction "R0(1)_2") (pintype "passive"))
      (node (ref "U11") (pin "3") (pinfunction "R0(2)_3") (pintype "passive"))
      (node (ref "U12") (pin "2") (pinfunction "R0(1)_2") (pintype "passive"))
      (node (ref "U12") (pin "3") (pinfunction "R0(2)_3") (pintype "passive"))
      (node (ref "U4") (pin "6") (pinfunction "6_6") (pintype "passive"))
    )
    (net (code "118") (name "Net-(U12-CP1..3)") (class "Default")
      (node (ref "U12") (pin "1") (pinfunction "CP1..3_1") (pintype "passive"))
      (node (ref "U12") (pin "12") (pinfunction "Q0_12") (pintype "passive"))
      (node (ref "U6") (pin "7") (pinfunction "A_7") (pintype "passive"))
    )
    (net (code "119") (name "Net-(U12-Q1)") (class "Default")
      (node (ref "U12") (pin "9") (pinfunction "Q1_9") (pintype "passive"))
      (node (ref "U4") (pin "2") (pinfunction "2_2") (pintype "passive"))
      (node (ref "U6") (pin "1") (pinfunction "B_1") (pintype "passive"))
    )
    (net (code "120") (name "Net-(U12-Q2)") (class "Default")
      (node (ref "U12") (pin "8") (pinfunction "Q2_8") (pintype "passive"))
      (node (ref "U2") (pin "9") (pinfunction "9_9") (pintype "passive"))
      (node (ref "U4") (pin "1") (pinfunction "1_1") (pintype "passive"))
      (node (ref "U6") (pin "2") (pinfunction "C_2") (pintype "passive"))
    )
    (net (code "121") (name "Net-(U12-Q3)") (class "Default")
      (node (ref "U12") (pin "11") (pinfunction "Q3_11") (pintype "passive"))
      (node (ref "U6") (pin "6") (pinfunction "D_6") (pintype "passive"))
    )
    (net (code "122") (name "Net-(U13-CP0)") (class "Default")
      (node (ref "U13") (pin "14") (pinfunction "CP0_14") (pintype "passive"))
      (node (ref "U4") (pin "8") (pinfunction "8_8") (pintype "passive"))
    )
    (net (code "123") (name "Net-(U13-CP1..3)") (class "Default")
      (node (ref "U13") (pin "1") (pinfunction "CP1..3_1") (pintype "passive"))
      (node (ref "U13") (pin "12") (pinfunction "Q0_12") (pintype "passive"))
      (node (ref "U7") (pin "7") (pinfunction "A_7") (pintype "passive"))
    )
    (net (code "124") (name "Net-(U13-Q1)") (class "Default")
      (node (ref "U13") (pin "9") (pinfunction "Q1_9") (pintype "passive"))
      (node (ref "U7") (pin "1") (pinfunction "B_1") (pintype "passive"))
    )
    (net (code "125") (name "Net-(U13-Q2)") (class "Default")
      (node (ref "U13") (pin "8") (pinfunction "Q2_8") (pintype "passive"))
      (node (ref "U7") (pin "2") (pinfunction "C_2") (pintype "passive"))
    )
    (net (code "126") (name "Net-(U13-Q3)") (class "Default")
      (node (ref "U13") (pin "11") (pinfunction "Q3_11") (pintype "passive"))
      (node (ref "U14") (pin "14") (pinfunction "CP0_14") (pintype "passive"))
      (node (ref "U7") (pin "6") (pinfunction "D_6") (pintype "passive"))
    )
    (net (code "127") (name "Net-(U14-CP1..3)") (class "Default")
      (node (ref "U14") (pin "1") (pinfunction "CP1..3_1") (pintype "passive"))
      (node (ref "U14") (pin "12") (pinfunction "Q0_12") (pintype "passive"))
      (node (ref "U8") (pin "7") (pinfunction "A_7") (pintype "passive"))
    )
    (net (code "128") (name "Net-(U14-Q1)") (class "Default")
      (node (ref "U14") (pin "3") (pinfunction "R0(2)_3") (pintype "passive"))
      (node (ref "U14") (pin "9") (pinfunction "Q1_9") (pintype "passive"))
      (node (ref "U8") (pin "1") (pinfunction "B_1") (pintype "passive"))
    )
    (net (code "129") (name "Net-(U14-Q2)") (class "Default")
      (node (ref "U14") (pin "2") (pinfunction "R0(1)_2") (pintype "passive"))
      (node (ref "U14") (pin "8") (pinfunction "Q2_8") (pintype "passive"))
      (node (ref "U3") (pin "9") (pinfunction "9_9") (pintype "passive"))
      (node (ref "U8") (pin "2") (pinfunction "C_2") (pintype "passive"))
    )
    (net (code "130") (name "Net-(U14-Q3)") (class "Default")
      (node (ref "U14") (pin "11") (pinfunction "Q3_11") (pintype "passive"))
      (node (ref "U8") (pin "6") (pinfunction "D_6") (pintype "passive"))
    )
    (net (code "131") (name "Net-(U15-CP0)") (class "Default")
      (node (ref "U15") (pin "14") (pinfunction "CP0_14") (pintype "passive"))
      (node (ref "U4") (pin "11") (pinfunction "11_11") (pintype "passive"))
    )
    (net (code "132") (name "Net-(U15-CP1..3)") (class "Default")
      (node (ref "U15") (pin "1") (pinfunction "CP1..3_1") (pintype "passive"))
      (node (ref "U15") (pin "12") (pinfunction "Q0_12") (pintype "passive"))
      (node (ref "U9") (pin "7") (pinfunction "A_7") (pintype "passive"))
    )
    (net (code "133") (name "Net-(U15-Q1)") (class "Default")
      (node (ref "U15") (pin "9") (pinfunction "Q1_9") (pintype "passive"))
      (node (ref "U9") (pin "1") (pinfunction "B_1") (pintype "passive"))
    )
    (net (code "134") (name "Net-(U15-Q2)") (class "Default")
      (node (ref "U15") (pin "2") (pinfunction "R0(1)_2") (pintype "passive"))
      (node (ref "U15") (pin "8") (pinfunction "Q2_8") (pintype "passive"))
      (node (ref "U16") (pin "2") (pinfunction "R0(1)_2") (pintype "passive"))
      (node (ref "U9") (pin "2") (pinfunction "C_2") (pintype "passive"))
    )
    (net (code "135") (name "Net-(U15-Q3)") (class "Default")
      (node (ref "U15") (pin "11") (pinfunction "Q3_11") (pintype "passive"))
      (node (ref "U16") (pin "1") (pinfunction "CP1..3_1") (pintype "passive"))
      (node (ref "U9") (pin "6") (pinfunction "D_6") (pintype "passive"))
    )
    (net (code "136") (name "VCC") (class "Default")
      (node (ref "C1") (pin "1") (pinfunction "1_1") (pintype "passive"))
      (node (ref "C10") (pin "1") (pinfunction "1_1") (pintype "passive"))
      (node (ref "C11") (pin "1") (pinfunction "1_1") (pintype "passive"))
      (node (ref "C12") (pin "1") (pinfunction "1_1") (pintype "passive"))
      (node (ref "C13") (pin "1") (pinfunction "1_1") (pintype "passive"))
      (node (ref "C14") (pin "1") (pinfunction "1_1") (pintype "passive"))
      (node (ref "C15") (pin "1") (pinfunction "1_1") (pintype "passive"))
      (node (ref "C16") (pin "1") (pinfunction "1_1") (pintype "passive"))
      (node (ref "C17") (pin "1") (pinfunction "1_1") (pintype "passive"))
      (node (ref "C2") (pin "1") (pinfunction "1_1") (pintype "passive"))
      (node (ref "C3") (pin "1") (pinfunction "1_1") (pintype "passive"))
      (node (ref "C4") (pin "1") (pinfunction "1_1") (pintype "passive"))
      (node (ref "C5") (pin "1") (pinfunction "1_1") (pintype "passive"))
      (node (ref "C6") (pin "1") (pinfunction "1_1") (pintype "passive"))
      (node (ref "C7") (pin "1") (pinfunction "1_1") (pintype "passive"))
      (node (ref "C8") (pin "1") (pinfunction "1_1") (pintype "passive"))
      (node (ref "C9") (pin "1") (pinfunction "1_1") (pintype "passive"))
      (node (ref "D1") (pin "2") (pinfunction "A_2") (pintype "passive"))
      (node (ref "D2") (pin "2") (pinfunction "A_2") (pintype "passive"))
      (node (ref "D3") (pin "2") (pinfunction "A_2") (pintype "passive"))
      (node (ref "D4") (pin "2") (pinfunction "A_2") (pintype "passive"))
      (node (ref "FLAG1") (pin "1") (pinfunction "pwr_1") (pintype "passive"))
      (node (ref "P1") (pin "1") (pinfunction "1_1") (pintype "passive"))
      (node (ref "R1") (pin "1") (pinfunction "1_1") (pintype "passive"))
      (node (ref "R2") (pin "1") (pinfunction "1_1") (pintype "passive"))
      (node (ref "R3") (pin "1") (pinfunction "1_1") (pintype "passive"))
      (node (ref "R4") (pin "1") (pinfunction "1_1") (pintype "passive"))
      (node (ref "R5") (pin "1") (pinfunction "1_1") (pintype "passive"))
      (node (ref "U1") (pin "16") (pinfunction "VCC_16") (pintype "passive"))
      (node (ref "U10") (pin "16") (pinfunction "VCC_16") (pintype "passive"))
      (node (ref "U10") (pin "3") (pinfunction "LT_3") (pintype "passive"))
      (node (ref "U11") (pin "5") (pinfunction "VCC_5") (pintype "passive"))
      (node (ref "U12") (pin "5") (pinfunction "VCC_5") (pintype "passive"))
      (node (ref "U13") (pin "5") (pinfunction "VCC_5") (pintype "passive"))
      (node (ref "U14") (pin "5") (pinfunction "VCC_5") (pintype "passive"))
      (node (ref "U15") (pin "5") (pinfunction "VCC_5") (pintype "passive"))
      (node (ref "U16") (pin "5") (pinfunction "VCC_5") (pintype "passive"))
      (node (ref "U17") (pin "13") (pinfunction "DIG2_CA_13") (pintype "passive"))
      (node (ref "U17") (pin "14") (pinfunction "DIG1_CA_14") (pintype "passive"))
      (node (ref "U18") (pin "13") (pinfunction "DIG2_CA_13") (pintype "passive"))
      (node (ref "U18") (pin "14") (pinfunction "DIG1_CA_14") (pintype "passive"))
      (node (ref "U19") (pin "13") (pinfunction "DIG2_CA_13") (pintype "passive"))
      (node (ref "U19") (pin "14") (pinfunction "DIG1_CA_14") (pintype "passive"))
      (node (ref "U2") (pin "14") (pinfunction "VCC_14") (pintype "passive"))
      (node (ref "U3") (pin "14") (pinfunction "VCC_14") (pintype "passive"))
      (node (ref "U4") (pin "14") (pinfunction "VCC_14") (pintype "passive"))
      (node (ref "U5") (pin "16") (pinfunction "VCC_16") (pintype "passive"))
      (node (ref "U5") (pin "3") (pinfunction "LT_3") (pintype "passive"))
      (node (ref "U5") (pin "5") (pinfunction "RBI_5") (pintype "passive"))
      (node (ref "U6") (pin "16") (pinfunction "VCC_16") (pintype "passive"))
      (node (ref "U6") (pin "3") (pinfunction "LT_3") (pintype "passive"))
      (node (ref "U6") (pin "5") (pinfunction "RBI_5") (pintype "passive"))
      (node (ref "U7") (pin "16") (pinfunction "VCC_16") (pintype "passive"))
      (node (ref "U7") (pin "3") (pinfunction "LT_3") (pintype "passive"))
      (node (ref "U7") (pin "5") (pinfunction "RBI_5") (pintype "passive"))
      (node (ref "U8") (pin "16") (pinfunction "VCC_16") (pintype "passive"))
      (node (ref "U9") (pin "16") (pinfunction "VCC_16") (pintype "passive"))
    )
    (net (code "137") (name "unconnected-(RP1-R8.1-Pad8)") (class "Default")
      (node (ref "RP1") (pin "8") (pinfunction "R8.1_8") (pintype "passive+no_connect"))
    )
    (net (code "138") (name "unconnected-(RP1-R8.2-Pad9)") (class "Default")
      (node (ref "RP1") (pin "9") (pinfunction "R8.2_9") (pintype "passive+no_connect"))
    )
    (net (code "139") (name "unconnected-(RP6-R8.1-Pad8)") (class "Default")
      (node (ref "RP6") (pin "8") (pinfunction "R8.1_8") (pintype "passive+no_connect"))
    )
    (net (code "140") (name "unconnected-(RP6-R8.2-Pad9)") (class "Default")
      (node (ref "RP6") (pin "9") (pinfunction "R8.2_9") (pintype "passive+no_connect"))
    )
    (net (code "141") (name "unconnected-(SW1-A-Pad3)") (class "Default")
      (node (ref "SW1") (pin "3") (pinfunction "A_3") (pintype "passive+no_connect"))
    )
    (net (code "142") (name "unconnected-(U1-CTC-Pad9)") (class "Default")
      (node (ref "U1") (pin "9") (pinfunction "CTC_9") (pintype "passive+no_connect"))
    )
    (net (code "143") (name "unconnected-(U1-Q3-Pad7)") (class "Default")
      (node (ref "U1") (pin "7") (pinfunction "Q3_7") (pintype "passive+no_connect"))
    )
    (net (code "144") (name "unconnected-(U1-Q4-Pad5)") (class "Default")
      (node (ref "U1") (pin "5") (pinfunction "Q4_5") (pintype "passive+no_connect"))
    )
    (net (code "145") (name "unconnected-(U1-Q5-Pad4)") (class "Default")
      (node (ref "U1") (pin "4") (pinfunction "Q5_4") (pintype "passive+no_connect"))
    )
    (net (code "146") (name "unconnected-(U1-Q6-Pad6)") (class "Default")
      (node (ref "U1") (pin "6") (pinfunction "Q6_6") (pintype "passive+no_connect"))
    )
    (net (code "147") (name "unconnected-(U1-Q7-Pad14)") (class "Default")
      (node (ref "U1") (pin "14") (pinfunction "Q7_14") (pintype "passive+no_connect"))
    )
    (net (code "148") (name "unconnected-(U1-Q8-Pad13)") (class "Default")
      (node (ref "U1") (pin "13") (pinfunction "Q8_13") (pintype "passive+no_connect"))
    )
    (net (code "149") (name "unconnected-(U1-Q9-Pad15)") (class "Default")
      (node (ref "U1") (pin "15") (pinfunction "Q9_15") (pintype "passive+no_connect"))
    )
    (net (code "150") (name "unconnected-(U1-Q11-Pad1)") (class "Default")
      (node (ref "U1") (pin "1") (pinfunction "Q11_1") (pintype "passive+no_connect"))
    )
    (net (code "151") (name "unconnected-(U1-Q12-Pad2)") (class "Default")
      (node (ref "U1") (pin "2") (pinfunction "Q12_2") (pintype "passive+no_connect"))
    )
    (net (code "152") (name "unconnected-(U5-BI-Pad4)") (class "Default")
      (node (ref "U5") (pin "4") (pinfunction "BI_4") (pintype "passive+no_connect"))
    )
    (net (code "153") (name "unconnected-(U6-BI-Pad4)") (class "Default")
      (node (ref "U6") (pin "4") (pinfunction "BI_4") (pintype "passive+no_connect"))
    )
    (net (code "154") (name "unconnected-(U7-BI-Pad4)") (class "Default")
      (node (ref "U7") (pin "4") (pinfunction "BI_4") (pintype "passive+no_connect"))
    )
    (net (code "155") (name "unconnected-(U8-BI-Pad4)") (class "Default")
      (node (ref "U8") (pin "4") (pinfunction "BI_4") (pintype "passive+no_connect"))
    )
    (net (code "156") (name "unconnected-(U9-BI-Pad4)") (class "Default")
      (node (ref "U9") (pin "4") (pinfunction "BI_4") (pintype "passive+no_connect"))
    )
    (net (code "157") (name "unconnected-(U10-BI-Pad4)") (class "Default")
      (node (ref "U10") (pin "4") (pinfunction "BI_4") (pintype "passive+no_connect"))
    )
    (net (code "158") (name "unconnected-(U17-DP1-Pad4)") (class "Default")
      (node (ref "U17") (pin "4") (pinfunction "DP1_4") (pintype "passive+no_connect"))
    )
    (net (code "159") (name "unconnected-(U17-DP2-Pad9)") (class "Default")
      (node (ref "U17") (pin "9") (pinfunction "DP2_9") (pintype "passive+no_connect"))
    )
    (net (code "160") (name "unconnected-(U18-DP1-Pad4)") (class "Default")
      (node (ref "U18") (pin "4") (pinfunction "DP1_4") (pintype "passive+no_connect"))
    )
    (net (code "161") (name "unconnected-(U18-DP2-Pad9)") (class "Default")
      (node (ref "U18") (pin "9") (pinfunction "DP2_9") (pintype "passive+no_connect"))
    )
    (net (code "162") (name "unconnected-(U19-DP1-Pad4)") (class "Default")
      (node (ref "U19") (pin "4") (pinfunction "DP1_4") (pintype "passive+no_connect"))
    )
    (net (code "163") (name "unconnected-(U19-DP2-Pad9)") (class "Default")
      (node (ref "U19") (pin "9") (pinfunction "DP2_9") (pintype "passive+no_connect"))
    )
  )
)
